# H0BR40.net
KiCad netlist of a schematic drawn in EAGLE
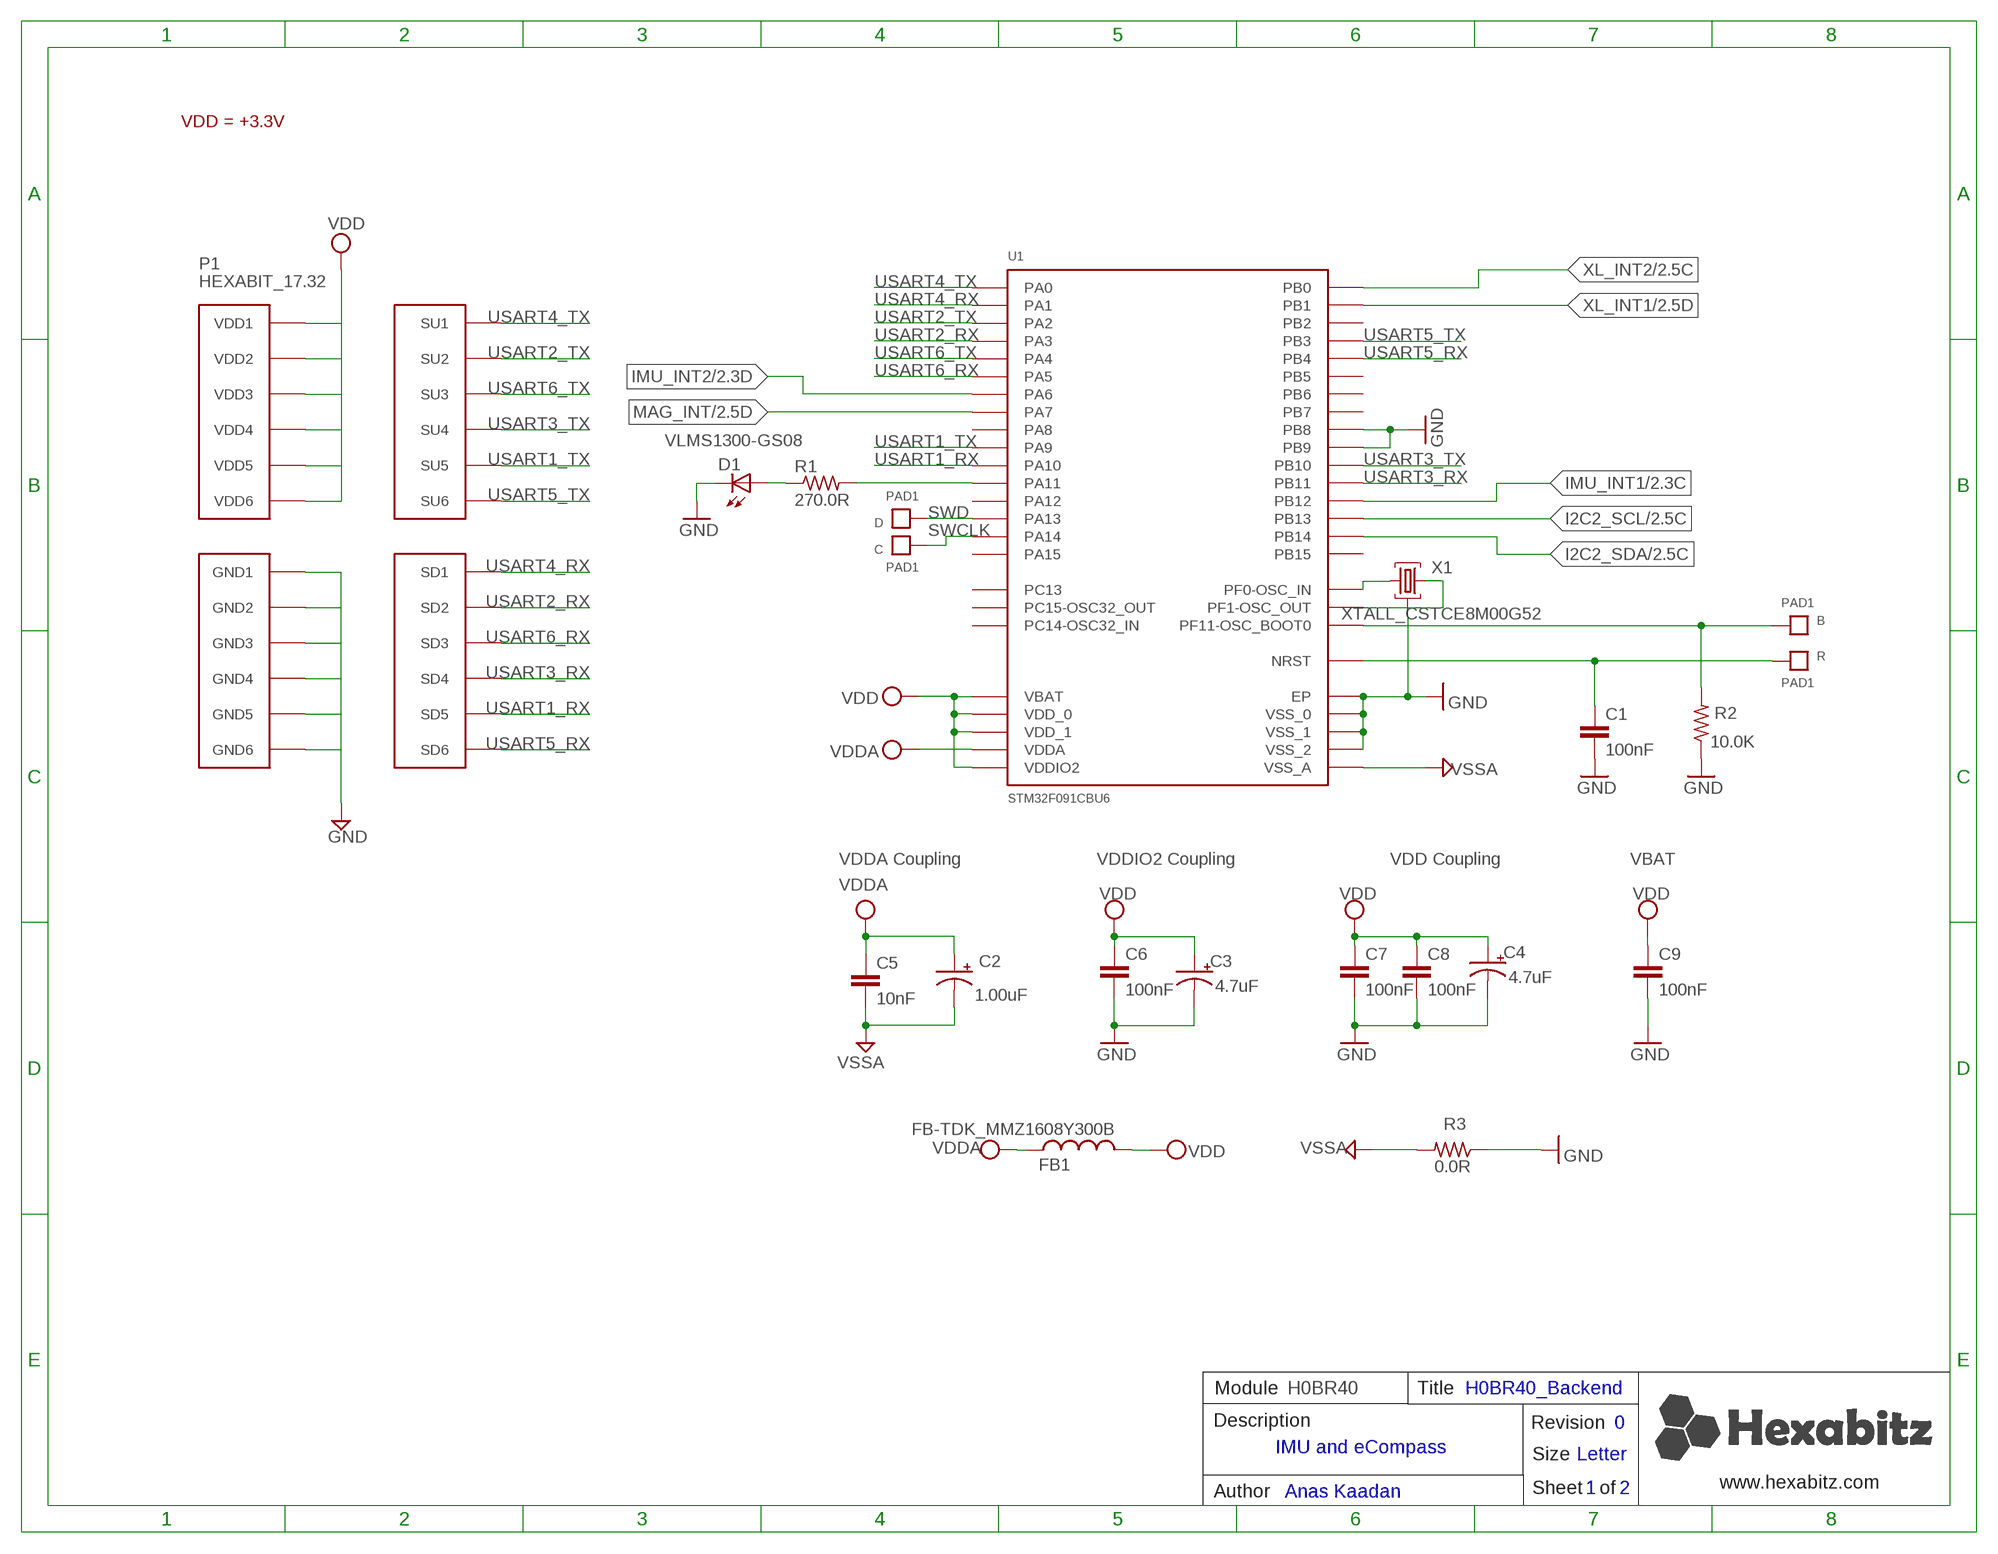
[diagram p0: schematic, sheet 1]
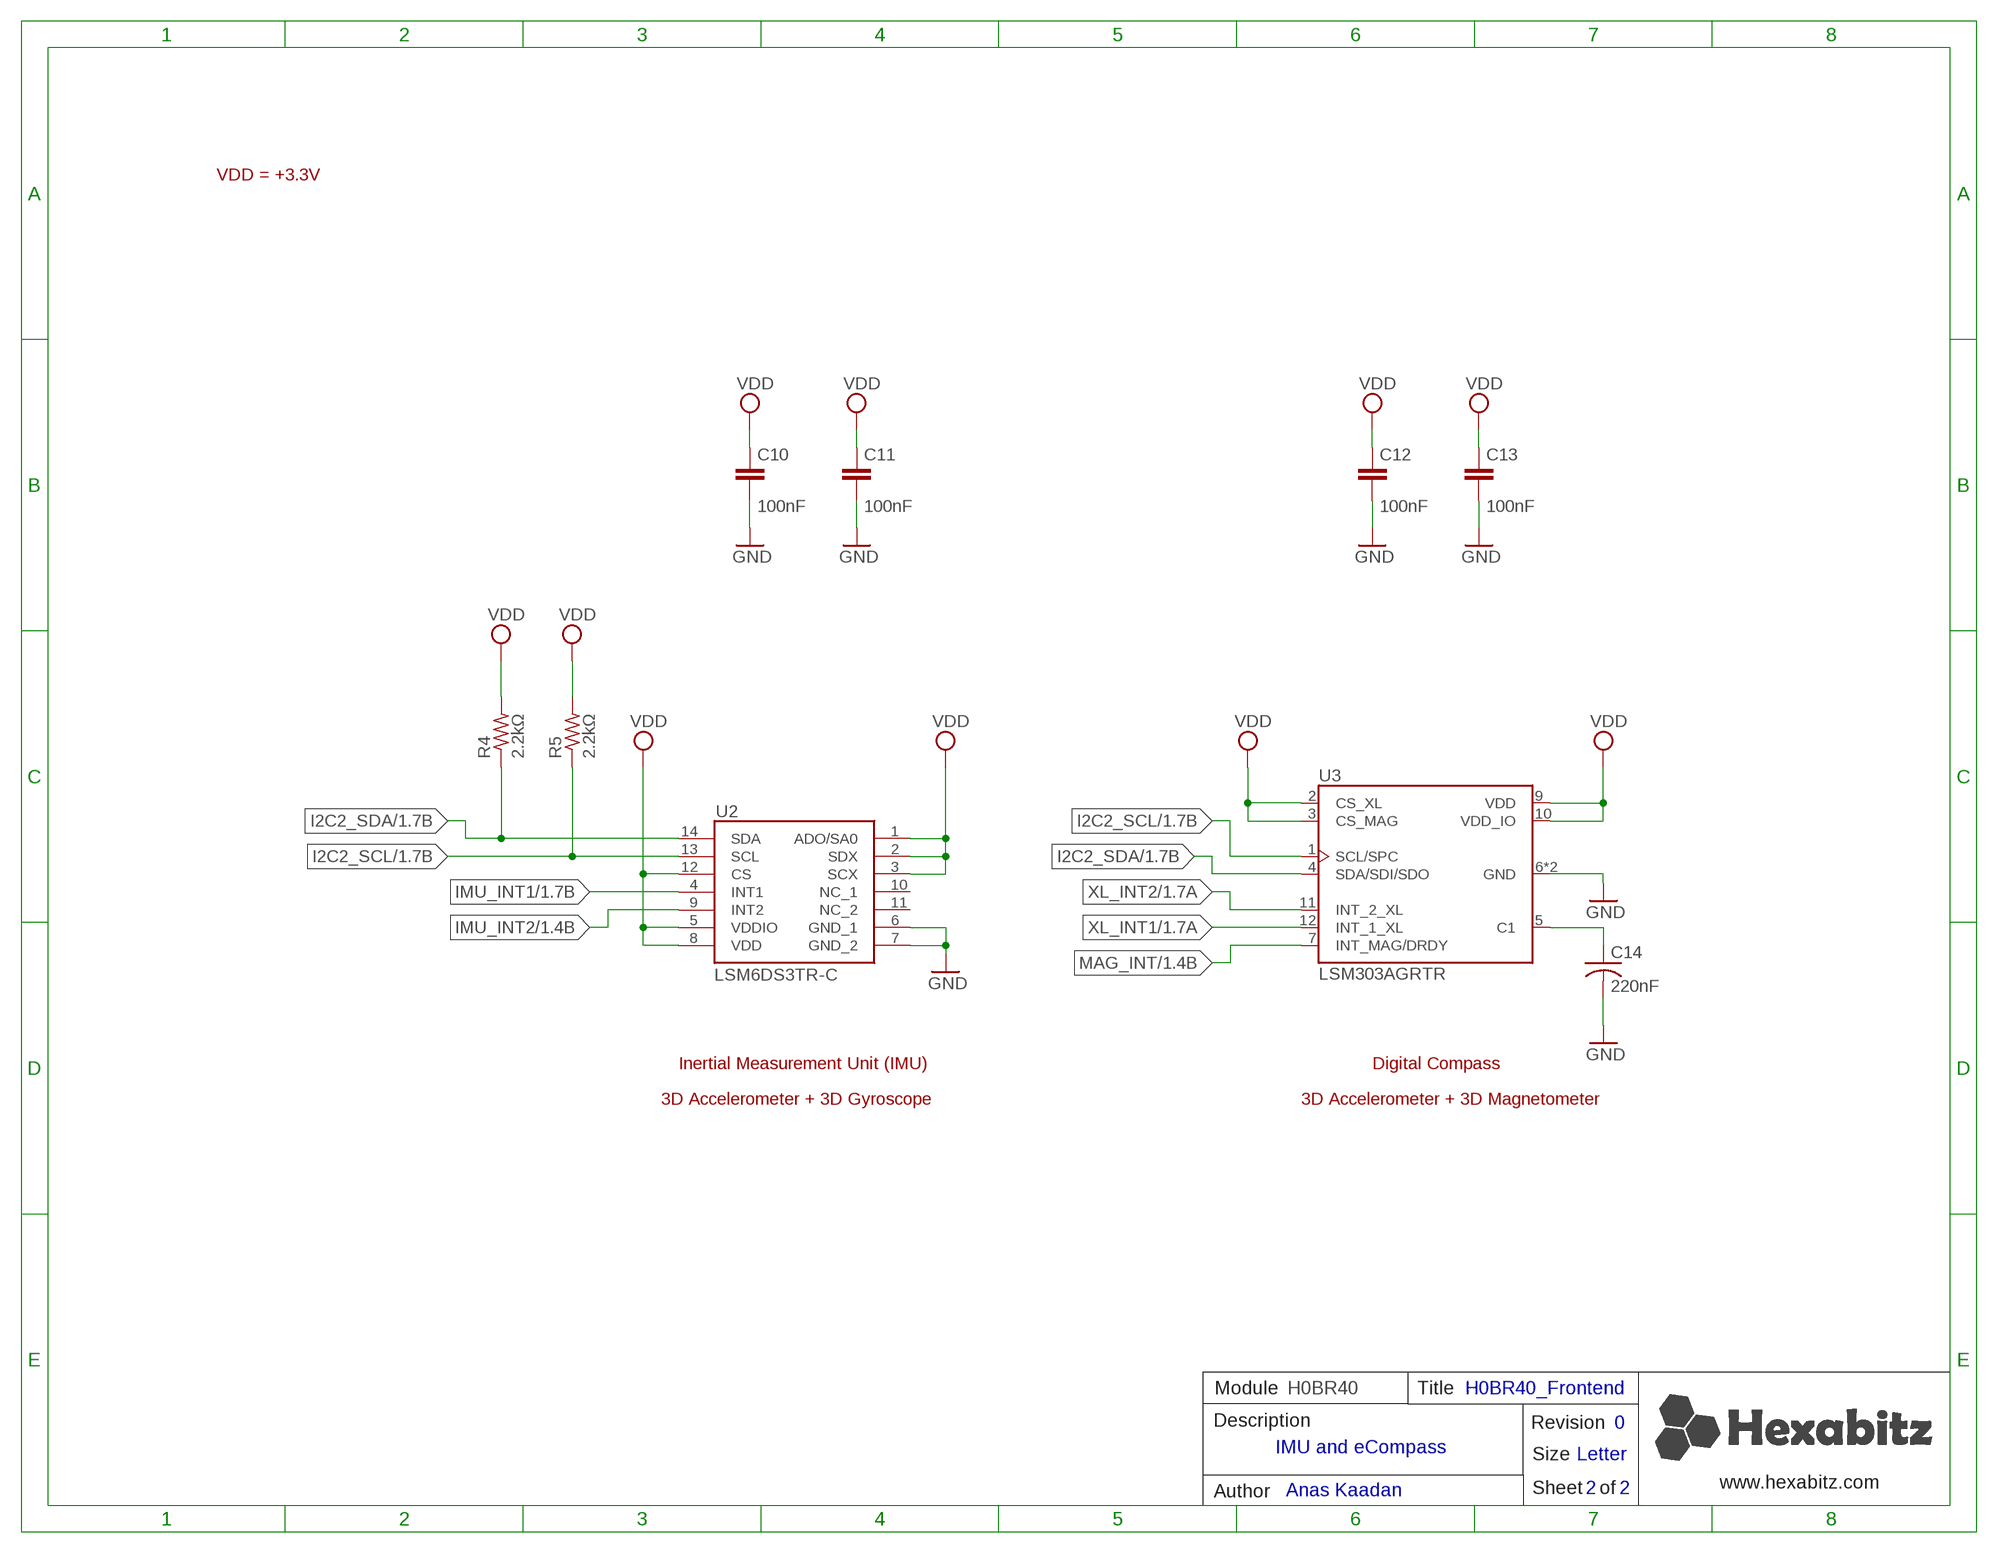
[diagram p1: schematic, sheet 2]

(export (version "E")
  (design (tool "Eeschema 10.0.6"))
  (components
    (comp (ref "B")
      (value "PAD1")
      (footprint "eagle-import:PAD1")
      (libsource (lib "eagle-import") (part "PAD1"))
    )
    (comp (ref "C")
      (value "PAD1")
      (footprint "eagle-import:PAD1")
      (libsource (lib "eagle-import") (part "PAD1"))
    )
    (comp (ref "C1")
      (value "100nF")
      (footprint "eagle-import:C-0603")
      (fields
        (field (name "CAPACITANCE") "100nF")
        (field (name "MFN") "AVX")
        (field (name "MPN") "0603YC104K4T2A")
        (field (name "OCTOPART_URL") "https://octopart.com/0603yc104k4t2a-avx+interconnect+%2F+elco-8120651")
        (field (name "TOLERANCE") "10%")
        (field (name "VOLTAGE_RATING") "16.0 V")
      )
      (libsource (lib "eagle-import") (part "C-0603"))
    )
    (comp (ref "C2")
      (value "1.00uF")
      (footprint "eagle-import:C-0805-POL")
      (fields
        (field (name "CAPACITANCE") "1.00uF")
        (field (name "MFN") "AVX")
        (field (name "MPN") "TAJR105M016RNJ")
        (field (name "OCTOPART_URL") "http://octopart.com/tajr105m016rnj-avx-1188552")
        (field (name "TOLERANCE") "10%")
        (field (name "VOLTAGE_RATING") "16.0 V")
      )
      (libsource (lib "eagle-import") (part "C-0805-POL"))
    )
    (comp (ref "C3")
      (value "4.7uF")
      (footprint "eagle-import:C-0805-POL")
      (fields
        (field (name "CAPACITANCE") "4.7uF")
        (field (name "MFN") "Panasonic")
        (field (name "MPN") "10TPU4R7MSI")
        (field (name "OCTOPART_URL") "https://octopart.com/10tpu4r7msi-panasonic-29487748")
        (field (name "TOLERANCE") "20%")
        (field (name "VOLTAGE_RATING") "10.0 V")
      )
      (libsource (lib "eagle-import") (part "C-0805-POL"))
    )
    (comp (ref "C4")
      (value "4.7uF")
      (footprint "eagle-import:C-0805-POL")
      (fields
        (field (name "CAPACITANCE") "4.7uF")
        (field (name "MFN") "Panasonic")
        (field (name "MPN") "10TPU4R7MSI")
        (field (name "OCTOPART_URL") "https://octopart.com/10tpu4r7msi-panasonic-29487748")
        (field (name "TOLERANCE") "10%")
        (field (name "VOLTAGE_RATING") "10 V")
      )
      (libsource (lib "eagle-import") (part "C-0805-POL"))
    )
    (comp (ref "C5")
      (value "10nF")
      (footprint "eagle-import:C-0603")
      (fields
        (field (name "CAPACITANCE") "10nF")
        (field (name "MFN") "AVX")
        (field (name "MPN") "0603YC103KAT4A")
        (field (name "OCTOPART_URL") "https://octopart.com/0603yc103kat4a-avx+interconnect+%2F+elco-2550362")
        (field (name "TOLERANCE") "10%")
        (field (name "VOLTAGE_RATING") "16.0 V")
      )
      (libsource (lib "eagle-import") (part "C-0603"))
    )
    (comp (ref "C6")
      (value "100nF")
      (footprint "eagle-import:C-0603")
      (fields
        (field (name "CAPACITANCE") "100nF")
        (field (name "MFN") "AVX")
        (field (name "MPN") "0603YC104K4T2A")
        (field (name "OCTOPART_URL") "https://octopart.com/0603yc104k4t2a-avx+interconnect+%2F+elco-8120651")
        (field (name "TOLERANCE") "10%")
        (field (name "VOLTAGE_RATING") "16.0 V")
      )
      (libsource (lib "eagle-import") (part "C-0603"))
    )
    (comp (ref "C7")
      (value "100nF")
      (footprint "eagle-import:C-0603")
      (fields
        (field (name "CAPACITANCE") "100nF")
        (field (name "MFN") "AVX")
        (field (name "MPN") "0603YC104K4T2A")
        (field (name "OCTOPART_URL") "https://octopart.com/0603yc104k4t2a-avx+interconnect+%2F+elco-8120651")
        (field (name "TOLERANCE") "10%")
        (field (name "VOLTAGE_RATING") "16.0 V")
      )
      (libsource (lib "eagle-import") (part "C-0603"))
    )
    (comp (ref "C8")
      (value "100nF")
      (footprint "eagle-import:C-0603")
      (fields
        (field (name "CAPACITANCE") "100nF")
        (field (name "MFN") "AVX")
        (field (name "MPN") "0603YC104K4T2A")
        (field (name "OCTOPART_URL") "https://octopart.com/0603yc104k4t2a-avx+interconnect+%2F+elco-8120651")
        (field (name "TOLERANCE") "10%")
        (field (name "VOLTAGE_RATING") "16.0 V")
      )
      (libsource (lib "eagle-import") (part "C-0603"))
    )
    (comp (ref "C9")
      (value "100nF")
      (footprint "eagle-import:C-0603")
      (fields
        (field (name "CAPACITANCE") "100nF")
        (field (name "MFN") "AVX")
        (field (name "MPN") "0603YC104K4T2A")
        (field (name "OCTOPART_URL") "https://octopart.com/0603yc104k4t2a-avx+interconnect+%2F+elco-8120651")
        (field (name "TOLERANCE") "16.0 V")
        (field (name "VOLTAGE_RATING") "10%")
      )
      (libsource (lib "eagle-import") (part "C-0603"))
    )
    (comp (ref "D")
      (value "PAD1")
      (footprint "eagle-import:PAD1")
      (libsource (lib "eagle-import") (part "PAD1"))
    )
    (comp (ref "D1")
      (value "VLMS1300-GS08")
      (footprint "eagle-import:VLMS1300-GS08")
      (fields
        (field (name "MFN") "Vishay")
        (field (name "MPN") "VLMS1300-GS08")
        (field (name "OCTOPART_URL") "https://octopart.com/vlms1300-gs08-vishay-21709201?r=sp&s=_gcP4_q8T1SC6PJQPTQ9yA")
      )
      (libsource (lib "eagle-import") (part "VLMS1300-GS08"))
    )
    (comp (ref "FB1")
      (value "FB-TDK_MMZ1608Y300B")
      (footprint "eagle-import:FB-TDK_MMZ1608Y300B")
      (fields
        (field (name "MFN") "TDK ")
        (field (name "MPN") "MMZ1608Y300B")
        (field (name "OCTOPART_URL") "https://octopart.com/mmz1608y300b-tdk-368280?r=sp&s=cd9_2ZEqQ9q9UNBuQgHAiA")
      )
      (libsource (lib "eagle-import") (part "FB-TDK_MMZ1608Y300B"))
    )
    (comp (ref "P1")
      (value "HEXABIT_17.32")
      (footprint "eagle-import:HEXABIT_17.32")
      (libsource (lib "eagle-import") (part "HEXABIT_?17.32"))
    )
    (comp (ref "R")
      (value "PAD1")
      (footprint "eagle-import:PAD1")
      (libsource (lib "eagle-import") (part "PAD1"))
    )
    (comp (ref "R1")
      (value "270.0R")
      (footprint "eagle-import:R-0603")
      (fields
        (field (name "MFN") "Panasonic")
        (field (name "MPN") "ERJ-3GEYJ271V")
        (field (name "OCTOPART_URL") "https://octopart.com/erj-3geyj271v-panasonic-55560546")
        (field (name "RESISTANCE") "270.0 Ohm")
        (field (name "TOLERANCE") "5%")
      )
      (libsource (lib "eagle-import") (part "R-0603"))
    )
    (comp (ref "R2")
      (value "10.0K")
      (footprint "eagle-import:R-0603")
      (fields
        (field (name "MFN") "Vishay")
        (field (name "MPN") "CRCW060310K0JNEB")
        (field (name "OCTOPART_URL") "https://octopart.com/crcw060310k0jneb-vishay-46603269")
        (field (name "RESISTANCE") "10.0K Ohm")
        (field (name "TOLERANCE") "5%")
      )
      (libsource (lib "eagle-import") (part "R-0603"))
    )
    (comp (ref "R3")
      (value "0.0R")
      (footprint "eagle-import:R-0603")
      (fields
        (field (name "MFN") "Vishay")
        (field (name "MPN") "CRCW06030000Z0EAHP")
        (field (name "OCTOPART_URL") "https://octopart.com/crcw06030000z0eahp-vishay-44320230")
        (field (name "RESISTANCE") "0.0 Ohm")
      )
      (libsource (lib "eagle-import") (part "R-0603"))
    )
    (comp (ref "U1")
      (value "STM32F091CBU6")
      (footprint "eagle-import:STM32F091CBU6")
      (libsource (lib "eagle-import") (part "STM32F091CBU6"))
    )
    (comp (ref "X1")
      (value "XTALL_CSTCE8M00G52")
      (footprint "eagle-import:XTALL_CSTCE8M00G52")
      (fields (field (name "MPN") "CSTCE8M00G52Z-R0"))
      (libsource (lib "eagle-import") (part "XTALL_CSTCE8M00G52"))
    )
    (comp (ref "C10")
      (value "100nF")
      (footprint "eagle-import:C-0603")
      (fields
        (field (name "CAPACITANCE") "100nF")
        (field (name "MFN") "AVX ")
        (field (name "MPN") "0603YC104K4T2A")
        (field (name "OCTOPART_URL") "https://octopart.com/0603yc104k4t2a-avx+interconnect+%2F+elco-8120651")
        (field (name "TOLERANCE") "±10%")
        (field (name "VOLTAGE_RATING") "16.0V")
      )
      (libsource (lib "eagle-import") (part "C-0603"))
    )
    (comp (ref "C11")
      (value "100nF")
      (footprint "eagle-import:C-0603")
      (fields
        (field (name "CAPACITANCE") "100nF")
        (field (name "MFN") "AVX ")
        (field (name "MPN") "0603YC104K4T2A")
        (field (name "OCTOPART_URL") "https://octopart.com/0603yc104k4t2a-avx+interconnect+%2F+elco-8120651")
        (field (name "TOLERANCE") "±10%")
        (field (name "VOLTAGE_RATING") "16.0V")
      )
      (libsource (lib "eagle-import") (part "C-0603"))
    )
    (comp (ref "C12")
      (value "100nF")
      (footprint "eagle-import:C-0603")
      (fields
        (field (name "CAPACITANCE") "100nF")
        (field (name "MFN") "AVX ")
        (field (name "MPN") "0603YC104K4T2A")
        (field (name "OCTOPART_URL") "https://octopart.com/0603yc104k4t2a-avx+interconnect+%2F+elco-8120651")
        (field (name "TOLERANCE") "±10%")
        (field (name "VOLTAGE_RATING") "16.0V")
      )
      (libsource (lib "eagle-import") (part "C-0603"))
    )
    (comp (ref "C13")
      (value "100nF")
      (footprint "eagle-import:C-0603")
      (fields
        (field (name "CAPACITANCE") "100nF")
        (field (name "MFN") "AVX ")
        (field (name "MPN") "0603YC104K4T2A")
        (field (name "OCTOPART_URL") "https://octopart.com/0603yc104k4t2a-avx+interconnect+%2F+elco-8120651")
        (field (name "TOLERANCE") "±10%")
        (field (name "VOLTAGE_RATING") "16.0V")
      )
      (libsource (lib "eagle-import") (part "C-0603"))
    )
    (comp (ref "C14")
      (value "220nF")
      (footprint "eagle-import:C-0805")
      (fields
        (field (name "CAPACITANCE") "220nF")
        (field (name "MFN") "KEMET ")
        (field (name "MPN") "C0805C224K1RACTU")
        (field (name "OCTOPAR_URL") "https://octopart.com/c0805c224k1ractu-kemet-12818106")
        (field (name "TOLERANCE") "±10%")
        (field (name "VOLTAGE_RATING") "100.0V")
      )
      (libsource (lib "eagle-import") (part "C-0805"))
    )
    (comp (ref "R4")
      (value "2.2kΩ")
      (footprint "eagle-import:R-0603")
      (fields
        (field (name "MFN") "Vishay ")
        (field (name "MPN") "CRCW06032K20FKEA")
        (field (name "OCTOPART_URL") "https://octopart.com/crcw06032k20fkea-vishay-40018987")
        (field (name "RESISTANCE") "2.2kΩ")
        (field (name "TOLERANCE") "±1%")
      )
      (libsource (lib "eagle-import") (part "R-0603"))
    )
    (comp (ref "R5")
      (value "2.2kΩ")
      (footprint "eagle-import:R-0603")
      (fields
        (field (name "MFN") "Vishay ")
        (field (name "MPN") "CRCW06032K20FKEA")
        (field (name "OCTOPART_URL") "https://octopart.com/crcw06032k20fkea-vishay-40018987")
        (field (name "RESISTANCE") "2.2 kΩ")
        (field (name "TOLERANCE") "±1%")
      )
      (libsource (lib "eagle-import") (part "R-0603"))
    )
    (comp (ref "U2")
      (value "LSM6DS3TR-C")
      (footprint "eagle-import:LGA-14(2.5X3X0.86)")
      (libsource (lib "eagle-import") (part "LSM6DS3TR-C"))
    )
    (comp (ref "U3")
      (value "LSM303AGRTR")
      (footprint "eagle-import:LGA12R50P_200X200X100")
      (libsource (lib "eagle-import") (part "LSM303AGRTR"))
    )
  )
  (nets
    (net (code "1") (name "GND") (class "Default")
      (node (ref "C1") (pin "2") (pinfunction "2_2") (pintype "passive"))
      (node (ref "C10") (pin "2") (pinfunction "2_2") (pintype "passive"))
      (node (ref "C11") (pin "2") (pinfunction "2_2") (pintype "passive"))
      (node (ref "C12") (pin "2") (pinfunction "2_2") (pintype "passive"))
      (node (ref "C13") (pin "2") (pinfunction "2_2") (pintype "passive"))
      (node (ref "C14") (pin "2") (pinfunction "2_2") (pintype "passive"))
      (node (ref "C3") (pin "2") (pinfunction "-_2") (pintype "passive"))
      (node (ref "C4") (pin "2") (pinfunction "-_2") (pintype "passive"))
      (node (ref "C6") (pin "2") (pinfunction "2_2") (pintype "passive"))
      (node (ref "C7") (pin "2") (pinfunction "2_2") (pintype "passive"))
      (node (ref "C8") (pin "2") (pinfunction "2_2") (pintype "passive"))
      (node (ref "C9") (pin "2") (pinfunction "2_2") (pintype "passive"))
      (node (ref "D1") (pin "C") (pinfunction "C_C") (pintype "passive"))
      (node (ref "P1") (pin "PAD_PD10") (pinfunction "GND4_PAD_PD10") (pintype "power_in"))
      (node (ref "P1") (pin "PAD_PD11") (pinfunction "GND5_PAD_PD11") (pintype "power_in"))
      (node (ref "P1") (pin "PAD_PD12") (pinfunction "GND6_PAD_PD12") (pintype "power_in"))
      (node (ref "P1") (pin "PAD_PD7") (pinfunction "GND1_PAD_PD7") (pintype "power_in"))
      (node (ref "P1") (pin "PAD_PD8") (pinfunction "GND2_PAD_PD8") (pintype "power_in"))
      (node (ref "P1") (pin "PAD_PD9") (pinfunction "GND3_PAD_PD9") (pintype "power_in"))
      (node (ref "R2") (pin "1") (pinfunction "1_1") (pintype "passive"))
      (node (ref "R3") (pin "1") (pinfunction "1_1") (pintype "passive"))
      (node (ref "U1") (pin "EP") (pinfunction "EP_EP") (pintype "power_in"))
      (node (ref "U1") (pin "P$23") (pinfunction "VSS_0_P$23") (pintype "power_in"))
      (node (ref "U1") (pin "P$35") (pinfunction "VSS_1_P$35") (pintype "power_in"))
      (node (ref "U1") (pin "P$45") (pinfunction "PB8_P$45") (pintype "bidirectional"))
      (node (ref "U1") (pin "P$46") (pinfunction "PB9_P$46") (pintype "bidirectional"))
      (node (ref "U1") (pin "P$47") (pinfunction "VSS_2_P$47") (pintype "power_in"))
      (node (ref "U2") (pin "6") (pinfunction "GND_1_6") (pintype "bidirectional"))
      (node (ref "U2") (pin "7") (pinfunction "GND_2_7") (pintype "bidirectional"))
      (node (ref "U3") (pin "6") (pinfunction "GND_6") (pintype "power_in"))
      (node (ref "U3") (pin "8") (pinfunction "GND_8") (pintype "power_in"))
      (node (ref "X1") (pin "P$2") (pinfunction "2_P$2") (pintype "passive"))
    )
    (net (code "2") (name "I2C2_SCL") (class "Default")
      (node (ref "R5") (pin "1") (pinfunction "1_1") (pintype "passive"))
      (node (ref "U1") (pin "P$26") (pinfunction "PB13_P$26") (pintype "bidirectional"))
      (node (ref "U2") (pin "13") (pinfunction "SCL_13") (pintype "bidirectional"))
      (node (ref "U3") (pin "1") (pinfunction "SCL/SPC_1") (pintype "bidirectional"))
    )
    (net (code "3") (name "I2C2_SDA") (class "Default")
      (node (ref "R4") (pin "1") (pinfunction "1_1") (pintype "passive"))
      (node (ref "U1") (pin "P$27") (pinfunction "PB14_P$27") (pintype "bidirectional"))
      (node (ref "U2") (pin "14") (pinfunction "SDA_14") (pintype "bidirectional"))
      (node (ref "U3") (pin "4") (pinfunction "SDA/SDI/SDO_4") (pintype "bidirectional"))
    )
    (net (code "4") (name "IMU_INT1") (class "Default")
      (node (ref "U1") (pin "P$25") (pinfunction "PB12_P$25") (pintype "bidirectional"))
      (node (ref "U2") (pin "4") (pinfunction "INT1_4") (pintype "bidirectional"))
    )
    (net (code "5") (name "IMU_INT2") (class "Default")
      (node (ref "U1") (pin "P$16") (pinfunction "PA6_P$16") (pintype "bidirectional"))
      (node (ref "U2") (pin "9") (pinfunction "INT2_9") (pintype "bidirectional"))
    )
    (net (code "6") (name "MAG_INT") (class "Default")
      (node (ref "U1") (pin "P$17") (pinfunction "PA7_P$17") (pintype "bidirectional"))
      (node (ref "U3") (pin "7") (pinfunction "INT_MAG/DRDY_7") (pintype "output"))
    )
    (net (code "7") (name "Net-(D1-PadA)") (class "Default")
      (node (ref "D1") (pin "A") (pinfunction "A_A") (pintype "passive"))
      (node (ref "R1") (pin "1") (pinfunction "1_1") (pintype "passive"))
    )
    (net (code "8") (name "Net-(U1-NRST)") (class "Default")
      (node (ref "C1") (pin "1") (pinfunction "1_1") (pintype "passive"))
      (node (ref "R") (pin "P$1") (pinfunction "P$1_P$1") (pintype "passive"))
      (node (ref "R") (pin "P$2") (pinfunction "P$1_P$2") (pintype "passive"))
      (node (ref "U1") (pin "P$7") (pinfunction "NRST_P$7") (pintype "passive"))
    )
    (net (code "9") (name "Net-(U1-PA11)") (class "Default")
      (node (ref "R1") (pin "2") (pinfunction "2_2") (pintype "passive"))
      (node (ref "U1") (pin "P$32") (pinfunction "PA11_P$32") (pintype "bidirectional"))
    )
    (net (code "10") (name "Net-(U1-PF0-OSC_IN)") (class "Default")
      (node (ref "U1") (pin "P$5") (pinfunction "PF0-OSC_IN_P$5") (pintype "bidirectional"))
      (node (ref "X1") (pin "P$1") (pinfunction "1_P$1") (pintype "passive"))
    )
    (net (code "11") (name "Net-(U1-PF1-OSC_OUT)") (class "Default")
      (node (ref "U1") (pin "P$6") (pinfunction "PF1-OSC_OUT_P$6") (pintype "bidirectional"))
      (node (ref "X1") (pin "P$3") (pinfunction "3_P$3") (pintype "passive"))
    )
    (net (code "12") (name "Net-(U1-PF11-OSC_BOOT0)") (class "Default")
      (node (ref "B") (pin "P$1") (pinfunction "P$1_P$1") (pintype "passive"))
      (node (ref "B") (pin "P$2") (pinfunction "P$1_P$2") (pintype "passive"))
      (node (ref "R2") (pin "2") (pinfunction "2_2") (pintype "passive"))
      (node (ref "U1") (pin "P$44") (pinfunction "PF11-OSC_BOOT0_P$44") (pintype "bidirectional"))
    )
    (net (code "13") (name "Net-(U3-C1)") (class "Default")
      (node (ref "C14") (pin "1") (pinfunction "1_1") (pintype "passive"))
      (node (ref "U3") (pin "5") (pinfunction "C1_5") (pintype "passive"))
    )
    (net (code "14") (name "SWCLK") (class "Default")
      (node (ref "C") (pin "P$1") (pinfunction "P$1_P$1") (pintype "passive"))
      (node (ref "C") (pin "P$2") (pinfunction "P$1_P$2") (pintype "passive"))
      (node (ref "U1") (pin "P$37") (pinfunction "PA14_P$37") (pintype "bidirectional"))
    )
    (net (code "15") (name "SWD") (class "Default")
      (node (ref "D") (pin "P$1") (pinfunction "P$1_P$1") (pintype "passive"))
      (node (ref "D") (pin "P$2") (pinfunction "P$1_P$2") (pintype "passive"))
      (node (ref "U1") (pin "P$34") (pinfunction "PA13_P$34") (pintype "bidirectional"))
    )
    (net (code "16") (name "USART1_RX") (class "Default")
      (node (ref "P1") (pin "PAD_PD5") (pinfunction "SD5_PAD_PD5") (pintype "bidirectional"))
      (node (ref "U1") (pin "P$31") (pinfunction "PA10_P$31") (pintype "bidirectional"))
    )
    (net (code "17") (name "USART1_TX") (class "Default")
      (node (ref "P1") (pin "PAD_PU5") (pinfunction "SU5_PAD_PU5") (pintype "bidirectional"))
      (node (ref "U1") (pin "P$30") (pinfunction "PA9_P$30") (pintype "bidirectional"))
    )
    (net (code "18") (name "USART2_RX") (class "Default")
      (node (ref "P1") (pin "PAD_PD2") (pinfunction "SD2_PAD_PD2") (pintype "bidirectional"))
      (node (ref "U1") (pin "P$13") (pinfunction "PA3_P$13") (pintype "bidirectional"))
    )
    (net (code "19") (name "USART2_TX") (class "Default")
      (node (ref "P1") (pin "PAD_PU2") (pinfunction "SU2_PAD_PU2") (pintype "bidirectional"))
      (node (ref "U1") (pin "P$12") (pinfunction "PA2_P$12") (pintype "bidirectional"))
    )
    (net (code "20") (name "USART3_RX") (class "Default")
      (node (ref "P1") (pin "PAD_PD4") (pinfunction "SD4_PAD_PD4") (pintype "bidirectional"))
      (node (ref "U1") (pin "P$22") (pinfunction "PB11_P$22") (pintype "bidirectional"))
    )
    (net (code "21") (name "USART3_TX") (class "Default")
      (node (ref "P1") (pin "PAD_PU4") (pinfunction "SU4_PAD_PU4") (pintype "bidirectional"))
      (node (ref "U1") (pin "P$21") (pinfunction "PB10_P$21") (pintype "bidirectional"))
    )
    (net (code "22") (name "USART4_RX") (class "Default")
      (node (ref "P1") (pin "PAD_PD1") (pinfunction "SD1_PAD_PD1") (pintype "bidirectional"))
      (node (ref "U1") (pin "P$11") (pinfunction "PA1_P$11") (pintype "bidirectional"))
    )
    (net (code "23") (name "USART4_TX") (class "Default")
      (node (ref "P1") (pin "PAD_PU1") (pinfunction "SU1_PAD_PU1") (pintype "bidirectional"))
      (node (ref "U1") (pin "P$10") (pinfunction "PA0_P$10") (pintype "bidirectional"))
    )
    (net (code "24") (name "USART5_RX") (class "Default")
      (node (ref "P1") (pin "PAD_PD6") (pinfunction "SD6_PAD_PD6") (pintype "bidirectional"))
      (node (ref "U1") (pin "P$40") (pinfunction "PB4_P$40") (pintype "bidirectional"))
    )
    (net (code "25") (name "USART5_TX") (class "Default")
      (node (ref "P1") (pin "PAD_PU6") (pinfunction "SU6_PAD_PU6") (pintype "bidirectional"))
      (node (ref "U1") (pin "P$39") (pinfunction "PB3_P$39") (pintype "bidirectional"))
    )
    (net (code "26") (name "USART6_RX") (class "Default")
      (node (ref "P1") (pin "PAD_PD3") (pinfunction "SD3_PAD_PD3") (pintype "bidirectional"))
      (node (ref "U1") (pin "P$15") (pinfunction "PA5_P$15") (pintype "bidirectional"))
    )
    (net (code "27") (name "USART6_TX") (class "Default")
      (node (ref "P1") (pin "PAD_PU3") (pinfunction "SU3_PAD_PU3") (pintype "bidirectional"))
      (node (ref "U1") (pin "P$14") (pinfunction "PA4_P$14") (pintype "bidirectional"))
    )
    (net (code "28") (name "VDD") (class "Default")
      (node (ref "C10") (pin "1") (pinfunction "1_1") (pintype "passive"))
      (node (ref "C11") (pin "1") (pinfunction "1_1") (pintype "passive"))
      (node (ref "C12") (pin "1") (pinfunction "1_1") (pintype "passive"))
      (node (ref "C13") (pin "1") (pinfunction "1_1") (pintype "passive"))
      (node (ref "C3") (pin "1") (pinfunction "+_1") (pintype "passive"))
      (node (ref "C4") (pin "1") (pinfunction "+_1") (pintype "passive"))
      (node (ref "C6") (pin "1") (pinfunction "1_1") (pintype "passive"))
      (node (ref "C7") (pin "1") (pinfunction "1_1") (pintype "passive"))
      (node (ref "C8") (pin "1") (pinfunction "1_1") (pintype "passive"))
      (node (ref "C9") (pin "1") (pinfunction "1_1") (pintype "passive"))
      (node (ref "FB1") (pin "2") (pinfunction "2_2") (pintype "passive"))
      (node (ref "P1") (pin "PAD_PU10") (pinfunction "VDD4_PAD_PU10") (pintype "power_in"))
      (node (ref "P1") (pin "PAD_PU11") (pinfunction "VDD5_PAD_PU11") (pintype "power_in"))
      (node (ref "P1") (pin "PAD_PU12") (pinfunction "VDD6_PAD_PU12") (pintype "power_in"))
      (node (ref "P1") (pin "PAD_PU7") (pinfunction "VDD1_PAD_PU7") (pintype "power_in"))
      (node (ref "P1") (pin "PAD_PU8") (pinfunction "VDD2_PAD_PU8") (pintype "power_in"))
      (node (ref "P1") (pin "PAD_PU9") (pinfunction "VDD3_PAD_PU9") (pintype "power_in"))
      (node (ref "R4") (pin "2") (pinfunction "2_2") (pintype "passive"))
      (node (ref "R5") (pin "2") (pinfunction "2_2") (pintype "passive"))
      (node (ref "U1") (pin "P$1") (pinfunction "VBAT_P$1") (pintype "power_in"))
      (node (ref "U1") (pin "P$24") (pinfunction "VDD_0_P$24") (pintype "power_in"))
      (node (ref "U1") (pin "P$36") (pinfunction "VDDIO2_P$36") (pintype "power_in"))
      (node (ref "U1") (pin "P$48") (pinfunction "VDD_1_P$48") (pintype "power_in"))
      (node (ref "U2") (pin "1") (pinfunction "ADO/SA0_1") (pintype "bidirectional"))
      (node (ref "U2") (pin "12") (pinfunction "CS_12") (pintype "bidirectional"))
      (node (ref "U2") (pin "2") (pinfunction "SDX_2") (pintype "bidirectional"))
      (node (ref "U2") (pin "3") (pinfunction "SCX_3") (pintype "bidirectional"))
      (node (ref "U2") (pin "5") (pinfunction "VDDIO_5") (pintype "bidirectional"))
      (node (ref "U2") (pin "8") (pinfunction "VDD_8") (pintype "bidirectional"))
      (node (ref "U3") (pin "10") (pinfunction "VDD_IO_10") (pintype "power_in"))
      (node (ref "U3") (pin "2") (pinfunction "CS_XL_2") (pintype "input"))
      (node (ref "U3") (pin "3") (pinfunction "CS_MAG_3") (pintype "input"))
      (node (ref "U3") (pin "9") (pinfunction "VDD_9") (pintype "power_in"))
    )
    (net (code "29") (name "VDDA") (class "Default")
      (node (ref "C2") (pin "1") (pinfunction "+_1") (pintype "passive"))
      (node (ref "C5") (pin "1") (pinfunction "1_1") (pintype "passive"))
      (node (ref "FB1") (pin "1") (pinfunction "1_1") (pintype "passive"))
      (node (ref "U1") (pin "P$9") (pinfunction "VDDA_P$9") (pintype "power_in"))
    )
    (net (code "30") (name "VSSA") (class "Default")
      (node (ref "C2") (pin "2") (pinfunction "-_2") (pintype "passive"))
      (node (ref "C5") (pin "2") (pinfunction "2_2") (pintype "passive"))
      (node (ref "R3") (pin "2") (pinfunction "2_2") (pintype "passive"))
      (node (ref "U1") (pin "P$8") (pinfunction "VSS_A_P$8") (pintype "power_in"))
    )
    (net (code "31") (name "XL_INT1") (class "Default")
      (node (ref "U1") (pin "P$19") (pinfunction "PB1_P$19") (pintype "bidirectional"))
      (node (ref "U3") (pin "12") (pinfunction "INT_1_XL_12") (pintype "output"))
    )
    (net (code "32") (name "XL_INT2") (class "Default")
      (node (ref "U1") (pin "P$18") (pinfunction "PB0_P$18") (pintype "bidirectional"))
      (node (ref "U3") (pin "11") (pinfunction "INT_2_XL_11") (pintype "output"))
    )
    (net (code "33") (name "unconnected-(U1-PA8-PadP$29)") (class "Default")
      (node (ref "U1") (pin "P$29") (pinfunction "PA8_P$29") (pintype "bidirectional"))
    )
    (net (code "34") (name "unconnected-(U1-PA12-PadP$33)") (class "Default")
      (node (ref "U1") (pin "P$33") (pinfunction "PA12_P$33") (pintype "bidirectional"))
    )
    (net (code "35") (name "unconnected-(U1-PA15-PadP$38)") (class "Default")
      (node (ref "U1") (pin "P$38") (pinfunction "PA15_P$38") (pintype "bidirectional"))
    )
    (net (code "36") (name "unconnected-(U1-PB2-PadP$20)") (class "Default")
      (node (ref "U1") (pin "P$20") (pinfunction "PB2_P$20") (pintype "bidirectional"))
    )
    (net (code "37") (name "unconnected-(U1-PB5-PadP$41)") (class "Default")
      (node (ref "U1") (pin "P$41") (pinfunction "PB5_P$41") (pintype "bidirectional"))
    )
    (net (code "38") (name "unconnected-(U1-PB6-PadP$42)") (class "Default")
      (node (ref "U1") (pin "P$42") (pinfunction "PB6_P$42") (pintype "bidirectional"))
    )
    (net (code "39") (name "unconnected-(U1-PB7-PadP$43)") (class "Default")
      (node (ref "U1") (pin "P$43") (pinfunction "PB7_P$43") (pintype "bidirectional"))
    )
    (net (code "40") (name "unconnected-(U1-PB15-PadP$28)") (class "Default")
      (node (ref "U1") (pin "P$28") (pinfunction "PB15_P$28") (pintype "bidirectional"))
    )
    (net (code "41") (name "unconnected-(U1-PC13-PadP$2)") (class "Default")
      (node (ref "U1") (pin "P$2") (pinfunction "PC13_P$2") (pintype "bidirectional"))
    )
    (net (code "42") (name "unconnected-(U1-PC14-OSC32_IN-PadP$3)") (class "Default")
      (node (ref "U1") (pin "P$3") (pinfunction "PC14-OSC32_IN_P$3") (pintype "bidirectional"))
    )
    (net (code "43") (name "unconnected-(U1-PC15-OSC32_OUT-PadP$4)") (class "Default")
      (node (ref "U1") (pin "P$4") (pinfunction "PC15-OSC32_OUT_P$4") (pintype "bidirectional"))
    )
    (net (code "44") (name "unconnected-(U2-NC_1-Pad10)") (class "Default")
      (node (ref "U2") (pin "10") (pinfunction "NC_1_10") (pintype "bidirectional"))
    )
    (net (code "45") (name "unconnected-(U2-NC_2-Pad11)") (class "Default")
      (node (ref "U2") (pin "11") (pinfunction "NC_2_11") (pintype "bidirectional"))
    )
  )
)
